# Quid_Sch_2023-09-17.net
KiCad netlist of a schematic drawn in Altium Designer
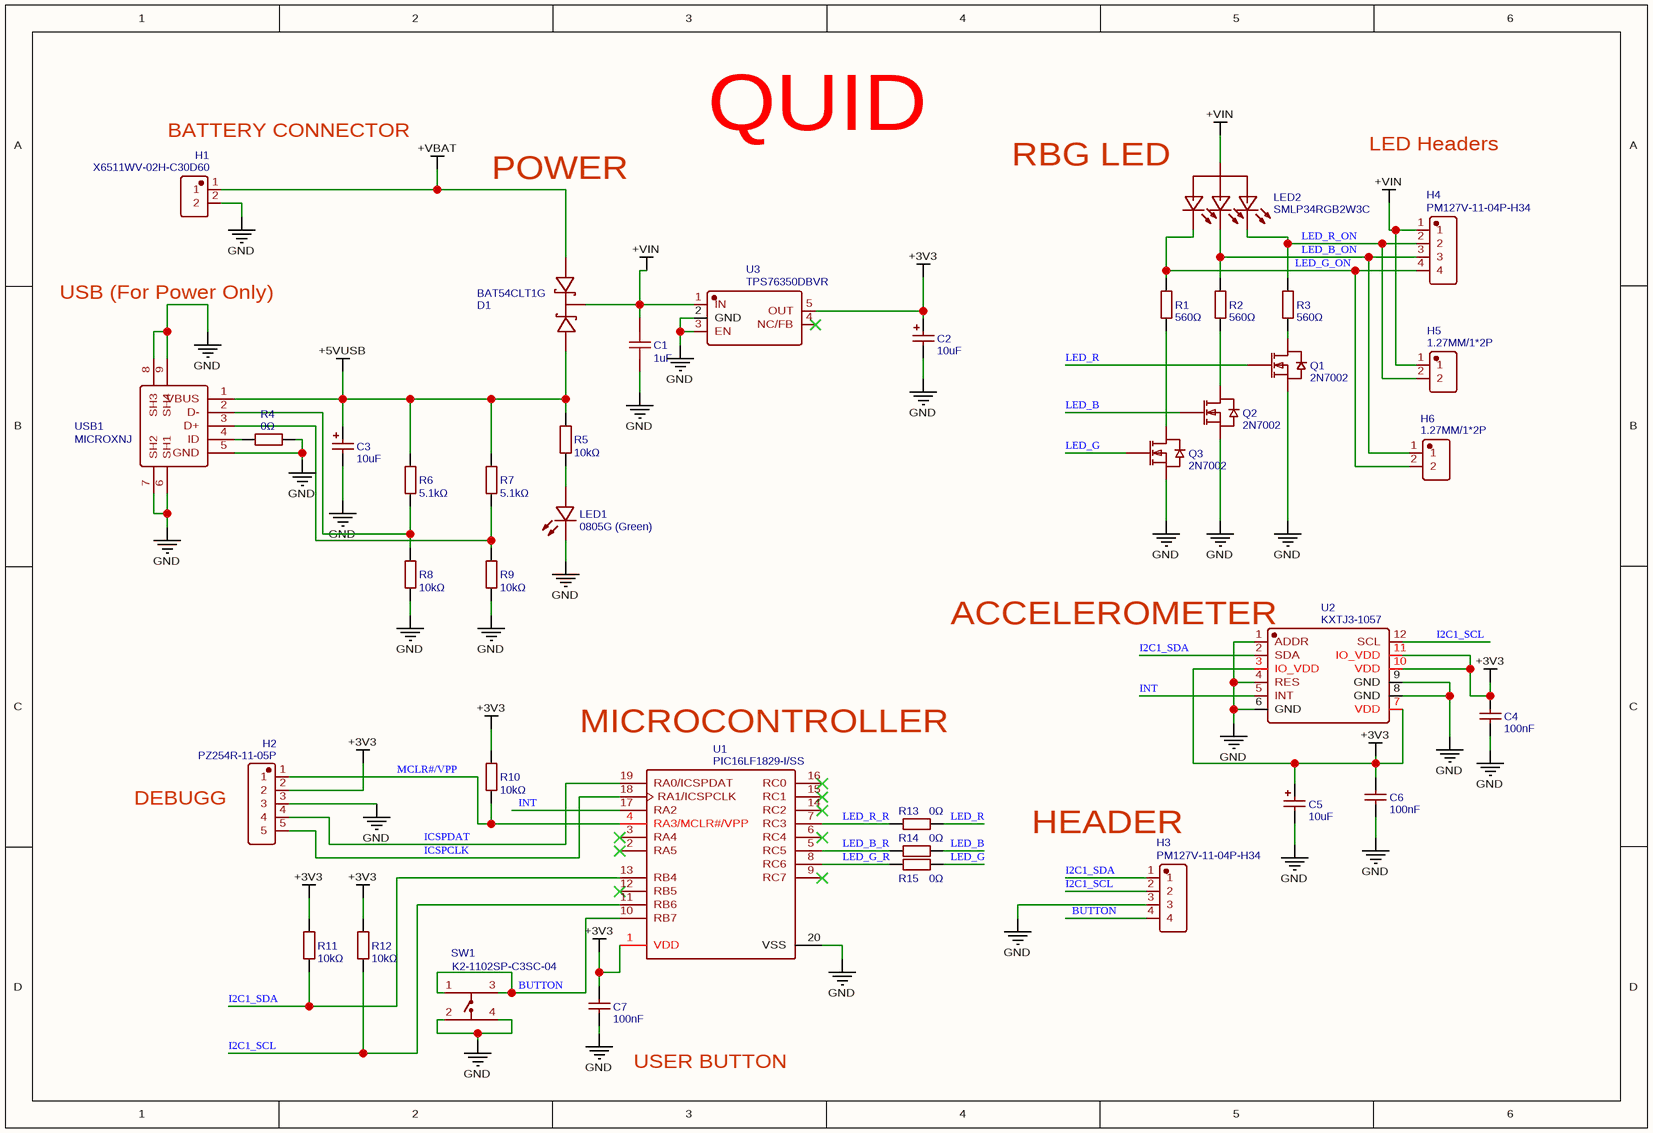
[diagram p0: Quid_Sch_2023-09-17.schdoc]

(export (version "E")
  (design (tool "Eeschema 10.0.6"))
  (components
    (comp (ref "C1")
      (value "1uF")
      (fields
        (field (name "MANUFACTURER") "SAMSUNG(三星)")
        (field (name "MANUFACTURER PART") "CL05A105KA5NQNC")
      )
      (libsource (lib "altium-import") (part "root_1_1uF_"))
    )
    (comp (ref "C2")
      (value "10uF")
      (fields (field (name "MANUFACTURER") "Kyocera AVX") (field (name "MANUFACTURER PART") "TAJA106K016RNJ"))
      (libsource (lib "altium-import") (part "root_1_10uF_"))
    )
    (comp (ref "C3")
      (value "10uF")
      (fields (field (name "MANUFACTURER") "Kyocera AVX") (field (name "MANUFACTURER PART") "TAJA106K016RNJ"))
      (libsource (lib "altium-import") (part "root_1_10uF_"))
    )
    (comp (ref "C4")
      (value "100nF")
      (fields
        (field (name "MANUFACTURER PART") "CL05B104KO5NNNC")
        (field (name "MANUFACTURER") "SAMSUNG(三星)")
      )
      (libsource (lib "altium-import") (part "root_1_100nF_"))
    )
    (comp (ref "C5")
      (value "10uF")
      (fields (field (name "MANUFACTURER") "Kyocera AVX") (field (name "MANUFACTURER PART") "TAJA106K016RNJ"))
      (libsource (lib "altium-import") (part "root_1_10uF_"))
    )
    (comp (ref "C6")
      (value "100nF")
      (fields
        (field (name "MANUFACTURER PART") "CL05B104KO5NNNC")
        (field (name "MANUFACTURER") "SAMSUNG(三星)")
      )
      (libsource (lib "altium-import") (part "root_1_100nF_"))
    )
    (comp (ref "C7")
      (value "100nF")
      (fields
        (field (name "MANUFACTURER PART") "CL05B104KO5NNNC")
        (field (name "MANUFACTURER") "SAMSUNG(三星)")
      )
      (libsource (lib "altium-import") (part "root_1_100nF_"))
    )
    (comp (ref "D1")
      (value "BAT54CLT1G")
      (fields (field (name "MANUFACTURER") "onsemi(安森美)"))
      (libsource (lib "altium-import") (part "root_1_BAT54CLT1G_"))
    )
    (comp (ref "H1")
      (value "X6511WV-02H-C30D60")
      (fields
        (field (name "MANUFACTURER") "XKB Connectivity(中国星坤)")
        (field (name "MANUFACTURER PART") "X6511WV-02H-C60D30")
        (field (name "CONTRIBUTOR") "LCSC")
      )
      (libsource (lib "altium-import") (part "root_0_X6511WV-02H-C30D60_"))
    )
    (comp (ref "H2")
      (value "PZ254R-11-05P")
      (fields (field (name "MANUFACTURER") "XFCN") (field (name "CONTRIBUTOR") "LCSC"))
      (libsource (lib "altium-import") (part "root_0_PZ254R-11-05P_"))
    )
    (comp (ref "H3")
      (value "PM127V-11-04P-H34")
      (fields (field (name "MANUFACTURER") "XFCN(兴飞)") (field (name "CONTRIBUTOR") "LCSC"))
      (libsource (lib "altium-import") (part "root_0_PM127V-11-04P-H34_"))
    )
    (comp (ref "H4")
      (value "PM127V-11-04P-H34")
      (fields (field (name "MANUFACTURER") "XFCN(兴飞)") (field (name "CONTRIBUTOR") "LCSC"))
      (libsource (lib "altium-import") (part "root_0_PM127V-11-04P-H34_"))
    )
    (comp (ref "H5")
      (value "1.27MM/1*2P")
      (fields
        (field (name "MANUFACTURER") "BOOMELE(博穆精密)")
        (field (name "MANUFACTURER PART") "1.27-1*2P针")
        (field (name "CONTRIBUTOR") "LCSC")
      )
      (libsource (lib "altium-import") (part "root_0_1.27MM/1*2P_"))
    )
    (comp (ref "H6")
      (value "1.27MM/1*2P")
      (fields
        (field (name "MANUFACTURER") "BOOMELE(博穆精密)")
        (field (name "MANUFACTURER PART") "1.27-1*2P针")
        (field (name "CONTRIBUTOR") "LCSC")
      )
      (libsource (lib "altium-import") (part "root_0_1.27MM/1*2P_"))
    )
    (comp (ref "LED1")
      (value "0805G (Green)")
      (fields (field (name "MANUFACTURER") "KENTO") (field (name "MANUFACTURER PART") "KT-0805翠绿"))
      (libsource (lib "altium-import") (part "root_1_0805G (Green)_"))
    )
    (comp (ref "LED2")
      (value "SMLP34RGB2W3C")
      (fields (field (name "MANUFACTURER") "ROHM(罗姆)") (field (name "CONTRIBUTOR") "LCSC"))
      (libsource (lib "altium-import") (part "root_2_SMLP34RGB2W3C_"))
    )
    (comp (ref "Q1")
      (value "2N7002")
      (fields (field (name "MANUFACTURER") "CJ(江苏长电/长晶)"))
      (libsource (lib "altium-import") (part "root_0_2N7002_"))
    )
    (comp (ref "Q2")
      (value "2N7002")
      (fields (field (name "MANUFACTURER") "CJ(江苏长电/长晶)"))
      (libsource (lib "altium-import") (part "root_0_2N7002_"))
    )
    (comp (ref "Q3")
      (value "2N7002")
      (fields (field (name "MANUFACTURER") "CJ(江苏长电/长晶)"))
      (libsource (lib "altium-import") (part "root_0_2N7002_"))
    )
    (comp (ref "R1")
      (value "560Ω")
      (fields
        (field (name "MANUFACTURER") "UNI-ROYAL(厚声)")
        (field (name "MANUFACTURER PART") "0402WGF5600TCE")
      )
      (libsource (lib "altium-import") (part "root_1_560Ω_"))
    )
    (comp (ref "R2")
      (value "560Ω")
      (fields
        (field (name "MANUFACTURER") "UNI-ROYAL(厚声)")
        (field (name "MANUFACTURER PART") "0402WGF5600TCE")
      )
      (libsource (lib "altium-import") (part "root_1_560Ω_"))
    )
    (comp (ref "R3")
      (value "560Ω")
      (fields
        (field (name "MANUFACTURER") "UNI-ROYAL(厚声)")
        (field (name "MANUFACTURER PART") "0402WGF5600TCE")
      )
      (libsource (lib "altium-import") (part "root_1_560Ω_"))
    )
    (comp (ref "R4")
      (value "0Ω")
      (fields
        (field (name "MANUFACTURER") "UNI-ROYAL(厚声)")
        (field (name "MANUFACTURER PART") "0402WGF0000TCE")
      )
      (libsource (lib "altium-import") (part "root_0_0Ω_"))
    )
    (comp (ref "R5")
      (value "10kΩ")
      (fields
        (field (name "MANUFACTURER") "UNI-ROYAL(厚声)")
        (field (name "MANUFACTURER PART") "0402WGF1002TCE")
      )
      (libsource (lib "altium-import") (part "root_1_10kΩ_"))
    )
    (comp (ref "R6")
      (value "5.1kΩ")
      (fields
        (field (name "MANUFACTURER") "UNI-ROYAL(厚声)")
        (field (name "MANUFACTURER PART") "0402WGF5101TCE")
      )
      (libsource (lib "altium-import") (part "root_1_5.1kΩ_"))
    )
    (comp (ref "R7")
      (value "5.1kΩ")
      (fields
        (field (name "MANUFACTURER") "UNI-ROYAL(厚声)")
        (field (name "MANUFACTURER PART") "0402WGF5101TCE")
      )
      (libsource (lib "altium-import") (part "root_1_5.1kΩ_"))
    )
    (comp (ref "R8")
      (value "10kΩ")
      (fields
        (field (name "MANUFACTURER") "UNI-ROYAL(厚声)")
        (field (name "MANUFACTURER PART") "0402WGF1002TCE")
      )
      (libsource (lib "altium-import") (part "root_1_10kΩ_"))
    )
    (comp (ref "R9")
      (value "10kΩ")
      (fields
        (field (name "MANUFACTURER") "UNI-ROYAL(厚声)")
        (field (name "MANUFACTURER PART") "0402WGF1002TCE")
      )
      (libsource (lib "altium-import") (part "root_1_10kΩ_"))
    )
    (comp (ref "R10")
      (value "10kΩ")
      (fields
        (field (name "MANUFACTURER") "UNI-ROYAL(厚声)")
        (field (name "MANUFACTURER PART") "0402WGF1002TCE")
      )
      (libsource (lib "altium-import") (part "root_1_10kΩ_"))
    )
    (comp (ref "R11")
      (value "10kΩ")
      (fields
        (field (name "MANUFACTURER") "UNI-ROYAL(厚声)")
        (field (name "MANUFACTURER PART") "0402WGF1002TCE")
      )
      (libsource (lib "altium-import") (part "root_1_10kΩ_"))
    )
    (comp (ref "R12")
      (value "10kΩ")
      (fields
        (field (name "MANUFACTURER") "UNI-ROYAL(厚声)")
        (field (name "MANUFACTURER PART") "0402WGF1002TCE")
      )
      (libsource (lib "altium-import") (part "root_1_10kΩ_"))
    )
    (comp (ref "R13")
      (value "0Ω")
      (fields
        (field (name "MANUFACTURER") "UNI-ROYAL(厚声)")
        (field (name "MANUFACTURER PART") "0402WGF0000TCE")
      )
      (libsource (lib "altium-import") (part "root_0_0Ω_"))
    )
    (comp (ref "R14")
      (value "0Ω")
      (fields
        (field (name "MANUFACTURER") "UNI-ROYAL(厚声)")
        (field (name "MANUFACTURER PART") "0402WGF0000TCE")
      )
      (libsource (lib "altium-import") (part "root_0_0Ω_"))
    )
    (comp (ref "R15")
      (value "0Ω")
      (fields
        (field (name "MANUFACTURER") "UNI-ROYAL(厚声)")
        (field (name "MANUFACTURER PART") "0402WGF0000TCE")
      )
      (libsource (lib "altium-import") (part "root_0_0Ω_"))
    )
    (comp (ref "SW1")
      (value "K2-1102SP-C3SC-04")
      (fields (field (name "MANUFACTURER") "韩国韩荣") (field (name "CONTRIBUTOR") "LCSC"))
      (libsource (lib "altium-import") (part "root_0_K2-1102SP-C3SC-04_"))
    )
    (comp (ref "U1")
      (value "PIC16LF1829-I/SS")
      (fields (field (name "MANUFACTURER") "MICROCHIP(美国微芯)"))
      (libsource (lib "altium-import") (part "root_0_PIC16LF1829-I/SS_"))
    )
    (comp (ref "U2")
      (value "KXTJ3-1057")
      (fields (field (name "MANUFACTURER") "ROHM(罗姆)") (field (name "CONTRIBUTOR") "LCSC"))
      (libsource (lib "altium-import") (part "root_0_KXTJ3-1057_"))
    )
    (comp (ref "U3")
      (value "TPS76350DBVR")
      (fields (field (name "MANUFACTURER") "TI(德州仪器)") (field (name "CONTRIBUTOR") "LCSC"))
      (libsource (lib "altium-import") (part "root_0_TPS76350DBVR_"))
    )
    (comp (ref "USB1")
      (value "MICROXNJ")
      (fields
        (field (name "MANUFACTURER") "SHOU HAN(首韩)")
        (field (name "MANUFACTURER PART") "MicroXNJ")
        (field (name "CONTRIBUTOR") "LCSC")
      )
      (libsource (lib "altium-import") (part "root_2_MICROXNJ_"))
    )
  )
  (nets
    (net (code "1") (name "+3V3") (class "Default")
      (node (ref "C2") (pin "1") (pinfunction "1_1") (pintype "passive"))
      (node (ref "C4") (pin "2") (pinfunction "2_2") (pintype "passive"))
      (node (ref "C5") (pin "1") (pinfunction "1_1") (pintype "passive"))
      (node (ref "C6") (pin "2") (pinfunction "2_2") (pintype "passive"))
      (node (ref "C7") (pin "2") (pinfunction "2_2") (pintype "passive"))
      (node (ref "H2") (pin "2") (pinfunction "2_2") (pintype "passive"))
      (node (ref "R10") (pin "2") (pinfunction "2_2") (pintype "passive"))
      (node (ref "R11") (pin "2") (pinfunction "2_2") (pintype "passive"))
      (node (ref "R12") (pin "2") (pinfunction "2_2") (pintype "passive"))
      (node (ref "U1") (pin "1") (pinfunction "VDD_1") (pintype "passive"))
      (node (ref "U2") (pin "10") (pinfunction "VDD_10") (pintype "passive"))
      (node (ref "U2") (pin "11") (pinfunction "IO_VDD_11") (pintype "passive"))
      (node (ref "U2") (pin "3") (pinfunction "IO_VDD_3") (pintype "passive"))
      (node (ref "U2") (pin "7") (pinfunction "VDD_7") (pintype "passive"))
      (node (ref "U3") (pin "5") (pinfunction "OUT_5") (pintype "passive"))
    )
    (net (code "2") (name "+5VUSB") (class "Default")
      (node (ref "C3") (pin "1") (pinfunction "1_1") (pintype "passive"))
      (node (ref "D1") (pin "2") (pinfunction "A_2") (pintype "passive"))
      (node (ref "R5") (pin "2") (pinfunction "2_2") (pintype "passive"))
      (node (ref "R6") (pin "2") (pinfunction "2_2") (pintype "passive"))
      (node (ref "R7") (pin "2") (pinfunction "2_2") (pintype "passive"))
      (node (ref "USB1") (pin "1") (pinfunction "VBUS_1") (pintype "passive"))
    )
    (net (code "3") (name "+VBAT") (class "Default")
      (node (ref "D1") (pin "1") (pinfunction "A_1") (pintype "passive"))
      (node (ref "H1") (pin "1") (pinfunction "1_1") (pintype "passive"))
    )
    (net (code "4") (name "+VIN") (class "Default")
      (node (ref "C1") (pin "2") (pinfunction "2_2") (pintype "passive"))
      (node (ref "D1") (pin "3") (pinfunction "K_3") (pintype "passive"))
      (node (ref "H4") (pin "1") (pinfunction "1_1") (pintype "passive"))
      (node (ref "H5") (pin "1") (pinfunction "1_1") (pintype "passive"))
      (node (ref "LED2") (pin "1") (pinfunction "COM_1") (pintype "passive"))
      (node (ref "U3") (pin "1") (pinfunction "IN_1") (pintype "passive"))
    )
    (net (code "5") (name "/BUTTON") (class "Default")
      (node (ref "H3") (pin "4") (pinfunction "4_4") (pintype "passive"))
      (node (ref "SW1") (pin "1") (pinfunction "1_1") (pintype "passive"))
      (node (ref "SW1") (pin "3") (pinfunction "3_3") (pintype "passive"))
      (node (ref "U1") (pin "10") (pinfunction "RB7_10") (pintype "passive"))
    )
    (net (code "6") (name "/I2C1_SCL") (class "Default")
      (node (ref "H3") (pin "2") (pinfunction "2_2") (pintype "passive"))
      (node (ref "R12") (pin "1") (pinfunction "1_1") (pintype "passive"))
      (node (ref "U1") (pin "11") (pinfunction "RB6_11") (pintype "passive"))
      (node (ref "U2") (pin "12") (pinfunction "SCL_12") (pintype "passive"))
    )
    (net (code "7") (name "/I2C1_SDA") (class "Default")
      (node (ref "H3") (pin "1") (pinfunction "1_1") (pintype "passive"))
      (node (ref "R11") (pin "1") (pinfunction "1_1") (pintype "passive"))
      (node (ref "U1") (pin "13") (pinfunction "RB4_13") (pintype "passive"))
      (node (ref "U2") (pin "2") (pinfunction "SDA_2") (pintype "passive"))
    )
    (net (code "8") (name "/ICSPCLK") (class "Default")
      (node (ref "H2") (pin "5") (pinfunction "5_5") (pintype "passive"))
      (node (ref "U1") (pin "18") (pinfunction "RA1/ICSPCLK_18") (pintype "passive"))
    )
    (net (code "9") (name "/ICSPDAT") (class "Default")
      (node (ref "H2") (pin "4") (pinfunction "4_4") (pintype "passive"))
      (node (ref "U1") (pin "19") (pinfunction "RA0/ICSPDAT_19") (pintype "passive"))
    )
    (net (code "10") (name "/INT") (class "Default")
      (node (ref "U1") (pin "17") (pinfunction "RA2_17") (pintype "passive"))
      (node (ref "U2") (pin "5") (pinfunction "INT_5") (pintype "passive"))
    )
    (net (code "11") (name "/LED_B") (class "Default")
      (node (ref "Q2") (pin "1") (pinfunction "G_1") (pintype "passive"))
      (node (ref "R14") (pin "2") (pinfunction "2_2") (pintype "passive"))
    )
    (net (code "12") (name "/LED_B_ON") (class "Default")
      (node (ref "H4") (pin "3") (pinfunction "3_3") (pintype "passive"))
      (node (ref "H6") (pin "1") (pinfunction "1_1") (pintype "passive"))
      (node (ref "LED2") (pin "3") (pinfunction "B-_3") (pintype "passive"))
      (node (ref "R2") (pin "2") (pinfunction "2_2") (pintype "passive"))
    )
    (net (code "13") (name "/LED_B_R") (class "Default")
      (node (ref "R14") (pin "1") (pinfunction "1_1") (pintype "passive"))
      (node (ref "U1") (pin "5") (pinfunction "RC5_5") (pintype "passive"))
    )
    (net (code "14") (name "/LED_G") (class "Default")
      (node (ref "Q3") (pin "1") (pinfunction "G_1") (pintype "passive"))
      (node (ref "R15") (pin "2") (pinfunction "2_2") (pintype "passive"))
    )
    (net (code "15") (name "/LED_G_ON") (class "Default")
      (node (ref "H4") (pin "4") (pinfunction "4_4") (pintype "passive"))
      (node (ref "H6") (pin "2") (pinfunction "2_2") (pintype "passive"))
      (node (ref "LED2") (pin "4") (pinfunction "G-_4") (pintype "passive"))
      (node (ref "R1") (pin "2") (pinfunction "2_2") (pintype "passive"))
    )
    (net (code "16") (name "/LED_G_R") (class "Default")
      (node (ref "R15") (pin "1") (pinfunction "1_1") (pintype "passive"))
      (node (ref "U1") (pin "8") (pinfunction "RC6_8") (pintype "passive"))
    )
    (net (code "17") (name "/LED_R") (class "Default")
      (node (ref "Q1") (pin "1") (pinfunction "G_1") (pintype "passive"))
      (node (ref "R13") (pin "2") (pinfunction "2_2") (pintype "passive"))
    )
    (net (code "18") (name "/LED_R_ON") (class "Default")
      (node (ref "H4") (pin "2") (pinfunction "2_2") (pintype "passive"))
      (node (ref "H5") (pin "2") (pinfunction "2_2") (pintype "passive"))
      (node (ref "LED2") (pin "2") (pinfunction "R-_2") (pintype "passive"))
      (node (ref "R3") (pin "2") (pinfunction "2_2") (pintype "passive"))
    )
    (net (code "19") (name "/LED_R_R") (class "Default")
      (node (ref "R13") (pin "1") (pinfunction "1_1") (pintype "passive"))
      (node (ref "U1") (pin "7") (pinfunction "RC3_7") (pintype "passive"))
    )
    (net (code "20") (name "/MCLR#{slash}VPP") (class "Default")
      (node (ref "H2") (pin "1") (pinfunction "1_1") (pintype "passive"))
      (node (ref "R10") (pin "1") (pinfunction "1_1") (pintype "passive"))
      (node (ref "U1") (pin "4") (pinfunction "RA3/MCLR#/VPP_4") (pintype "passive"))
    )
    (net (code "21") (name "GND") (class "Default")
      (node (ref "C1") (pin "1") (pinfunction "1_1") (pintype "passive"))
      (node (ref "C2") (pin "2") (pinfunction "2_2") (pintype "passive"))
      (node (ref "C3") (pin "2") (pinfunction "2_2") (pintype "passive"))
      (node (ref "C4") (pin "1") (pinfunction "1_1") (pintype "passive"))
      (node (ref "C5") (pin "2") (pinfunction "2_2") (pintype "passive"))
      (node (ref "C6") (pin "1") (pinfunction "1_1") (pintype "passive"))
      (node (ref "C7") (pin "1") (pinfunction "1_1") (pintype "passive"))
      (node (ref "H1") (pin "2") (pinfunction "2_2") (pintype "passive"))
      (node (ref "H2") (pin "3") (pinfunction "3_3") (pintype "passive"))
      (node (ref "H3") (pin "3") (pinfunction "3_3") (pintype "passive"))
      (node (ref "LED1") (pin "2") (pinfunction "K_2") (pintype "passive"))
      (node (ref "Q1") (pin "2") (pinfunction "S_2") (pintype "passive"))
      (node (ref "Q2") (pin "2") (pinfunction "S_2") (pintype "passive"))
      (node (ref "Q3") (pin "2") (pinfunction "S_2") (pintype "passive"))
      (node (ref "R4") (pin "2") (pinfunction "2_2") (pintype "passive"))
      (node (ref "R8") (pin "1") (pinfunction "1_1") (pintype "passive"))
      (node (ref "R9") (pin "1") (pinfunction "1_1") (pintype "passive"))
      (node (ref "SW1") (pin "2") (pinfunction "2_2") (pintype "passive"))
      (node (ref "SW1") (pin "4") (pinfunction "4_4") (pintype "passive"))
      (node (ref "U1") (pin "20") (pinfunction "VSS_20") (pintype "passive"))
      (node (ref "U2") (pin "1") (pinfunction "ADDR_1") (pintype "passive"))
      (node (ref "U2") (pin "4") (pinfunction "RES_4") (pintype "passive"))
      (node (ref "U2") (pin "6") (pinfunction "GND_6") (pintype "passive"))
      (node (ref "U2") (pin "8") (pinfunction "GND_8") (pintype "passive"))
      (node (ref "U2") (pin "9") (pinfunction "GND_9") (pintype "passive"))
      (node (ref "U3") (pin "2") (pinfunction "GND_2") (pintype "passive"))
      (node (ref "U3") (pin "3") (pinfunction "EN_3") (pintype "passive"))
      (node (ref "USB1") (pin "5") (pinfunction "GND_5") (pintype "passive"))
      (node (ref "USB1") (pin "6") (pinfunction "SH1_6") (pintype "passive"))
      (node (ref "USB1") (pin "7") (pinfunction "SH2_7") (pintype "passive"))
      (node (ref "USB1") (pin "8") (pinfunction "SH3_8") (pintype "passive"))
      (node (ref "USB1") (pin "9") (pinfunction "SH4_9") (pintype "passive"))
    )
    (net (code "22") (name "Net-(LED1-A)") (class "Default")
      (node (ref "LED1") (pin "1") (pinfunction "A_1") (pintype "passive"))
      (node (ref "R5") (pin "1") (pinfunction "1_1") (pintype "passive"))
    )
    (net (code "23") (name "Net-(Q1-D)") (class "Default")
      (node (ref "Q1") (pin "3") (pinfunction "D_3") (pintype "passive"))
      (node (ref "R3") (pin "1") (pinfunction "1_1") (pintype "passive"))
    )
    (net (code "24") (name "Net-(Q2-D)") (class "Default")
      (node (ref "Q2") (pin "3") (pinfunction "D_3") (pintype "passive"))
      (node (ref "R2") (pin "1") (pinfunction "1_1") (pintype "passive"))
    )
    (net (code "25") (name "Net-(Q3-D)") (class "Default")
      (node (ref "Q3") (pin "3") (pinfunction "D_3") (pintype "passive"))
      (node (ref "R1") (pin "1") (pinfunction "1_1") (pintype "passive"))
    )
    (net (code "26") (name "Net-(USB1-D+)") (class "Default")
      (node (ref "R7") (pin "1") (pinfunction "1_1") (pintype "passive"))
      (node (ref "R9") (pin "2") (pinfunction "2_2") (pintype "passive"))
      (node (ref "USB1") (pin "3") (pinfunction "D+_3") (pintype "passive"))
    )
    (net (code "27") (name "Net-(USB1-D-)") (class "Default")
      (node (ref "R6") (pin "1") (pinfunction "1_1") (pintype "passive"))
      (node (ref "R8") (pin "2") (pinfunction "2_2") (pintype "passive"))
      (node (ref "USB1") (pin "2") (pinfunction "D-_2") (pintype "passive"))
    )
    (net (code "28") (name "Net-(USB1-ID)") (class "Default")
      (node (ref "R4") (pin "1") (pinfunction "1_1") (pintype "passive"))
      (node (ref "USB1") (pin "4") (pinfunction "ID_4") (pintype "passive"))
    )
    (net (code "29") (name "unconnected-(U1-RA4-Pad3)") (class "Default")
      (node (ref "U1") (pin "3") (pinfunction "RA4_3") (pintype "passive+no_connect"))
    )
    (net (code "30") (name "unconnected-(U1-RA5-Pad2)") (class "Default")
      (node (ref "U1") (pin "2") (pinfunction "RA5_2") (pintype "passive+no_connect"))
    )
    (net (code "31") (name "unconnected-(U1-RB5-Pad12)") (class "Default")
      (node (ref "U1") (pin "12") (pinfunction "RB5_12") (pintype "passive+no_connect"))
    )
    (net (code "32") (name "unconnected-(U1-RC0-Pad16)") (class "Default")
      (node (ref "U1") (pin "16") (pinfunction "RC0_16") (pintype "passive+no_connect"))
    )
    (net (code "33") (name "unconnected-(U1-RC1-Pad15)") (class "Default")
      (node (ref "U1") (pin "15") (pinfunction "RC1_15") (pintype "passive+no_connect"))
    )
    (net (code "34") (name "unconnected-(U1-RC2-Pad14)") (class "Default")
      (node (ref "U1") (pin "14") (pinfunction "RC2_14") (pintype "passive+no_connect"))
    )
    (net (code "35") (name "unconnected-(U1-RC4-Pad6)") (class "Default")
      (node (ref "U1") (pin "6") (pinfunction "RC4_6") (pintype "passive+no_connect"))
    )
    (net (code "36") (name "unconnected-(U1-RC7-Pad9)") (class "Default")
      (node (ref "U1") (pin "9") (pinfunction "RC7_9") (pintype "passive+no_connect"))
    )
    (net (code "37") (name "unconnected-(U3-NC{slash}FB-Pad4)") (class "Default")
      (node (ref "U3") (pin "4") (pinfunction "NC/FB_4") (pintype "passive+no_connect"))
    )
  )
)
